# Linear_Pos_regulator.net
KiCad netlist of a schematic drawn in Altium Designer
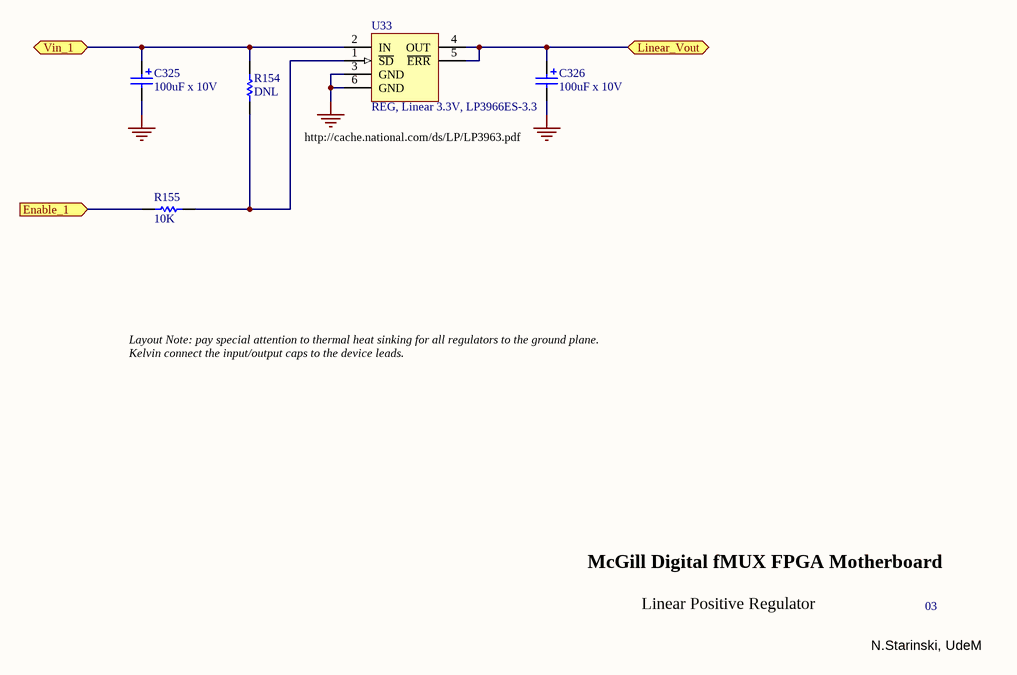
[diagram p0: Linear_Pos_regulator.SchDoc]

(export (version "E")
  (design (tool "Eeschema 10.0.6"))
  (components
    (comp (ref "C325")
      (value "100uF x 10V")
      (footprint "TC6032-2412")
      (description "CAP TANTC TPSC107K010R0075")
      (fields (field (name "PUBLISHER") "Altium Limited"))
      (libsource (lib "Miscellaneous Devices 02") (part "Cap Pol3"))
    )
    (comp (ref "C326")
      (value "100uF x 10V")
      (footprint "TC6032-2412")
      (description "CAP TANTC TPSC107K010R0075")
      (fields (field (name "PUBLISHER") "Altium Limited"))
      (libsource (lib "Miscellaneous Devices 02") (part "Cap Pol3"))
    )
    (comp (ref "R154")
      (value "DNL")
      (footprint "CR1608-0603")
      (description "Semiconductor Resistor")
      (fields (field (name "PUBLISHER") "Altium Limited"))
      (libsource (lib "Miscellaneous Devices") (part "Res Semi"))
    )
    (comp (ref "R155")
      (value "10K")
      (footprint "CR1608-0603")
      (description "Resistor 0603")
      (fields (field (name "PUBLISHER") "Altium Limited"))
      (libsource (lib "Miscellaneous Devices") (part "Res Semi"))
    )
    (comp (ref "U33")
      (value "REG, Linear 3.3V, LP3966ES-3.3")
      (footprint "TS5B")
      (description "3A Fast Ultra Low Dropout Linear Regulator")
      (libsource (lib "NSC Power Mgt Voltage Regulator") (part "LP3966"))
    )
  )
  (nets
    (net (code "1") (name "/Enable_1") (class "Default")
      (node (ref "R155") (pin "1") (pinfunction "1_1") (pintype "passive"))
    )
    (net (code "2") (name "/Linear_Vout") (class "Default")
      (node (ref "C326") (pin "1") (pinfunction "1_1") (pintype "passive"))
      (node (ref "U33") (pin "4") (pinfunction "OUT_4") (pintype "power_in"))
      (node (ref "U33") (pin "5") (pinfunction "~{ERR}_5") (pintype "passive"))
    )
    (net (code "3") (name "/Vin_1") (class "Default")
      (node (ref "C325") (pin "1") (pinfunction "1_1") (pintype "passive"))
      (node (ref "R154") (pin "2") (pinfunction "2_2") (pintype "passive"))
      (node (ref "U33") (pin "2") (pinfunction "IN_2") (pintype "power_in"))
    )
    (net (code "4") (name "GND") (class "Default")
      (node (ref "C325") (pin "2") (pinfunction "2_2") (pintype "passive"))
      (node (ref "C326") (pin "2") (pinfunction "2_2") (pintype "passive"))
      (node (ref "U33") (pin "3") (pinfunction "GND_3") (pintype "power_in"))
      (node (ref "U33") (pin "6") (pinfunction "GND_6") (pintype "power_in"))
    )
    (net (code "5") (name "Net-(U33-~{SD})") (class "Default")
      (node (ref "R154") (pin "1") (pinfunction "1_1") (pintype "passive"))
      (node (ref "R155") (pin "2") (pinfunction "2_2") (pintype "passive"))
      (node (ref "U33") (pin "1") (pinfunction "~{SD}_1") (pintype "input"))
    )
  )
)
